# memory.net
KiCad netlist of a schematic drawn in Altium Designer
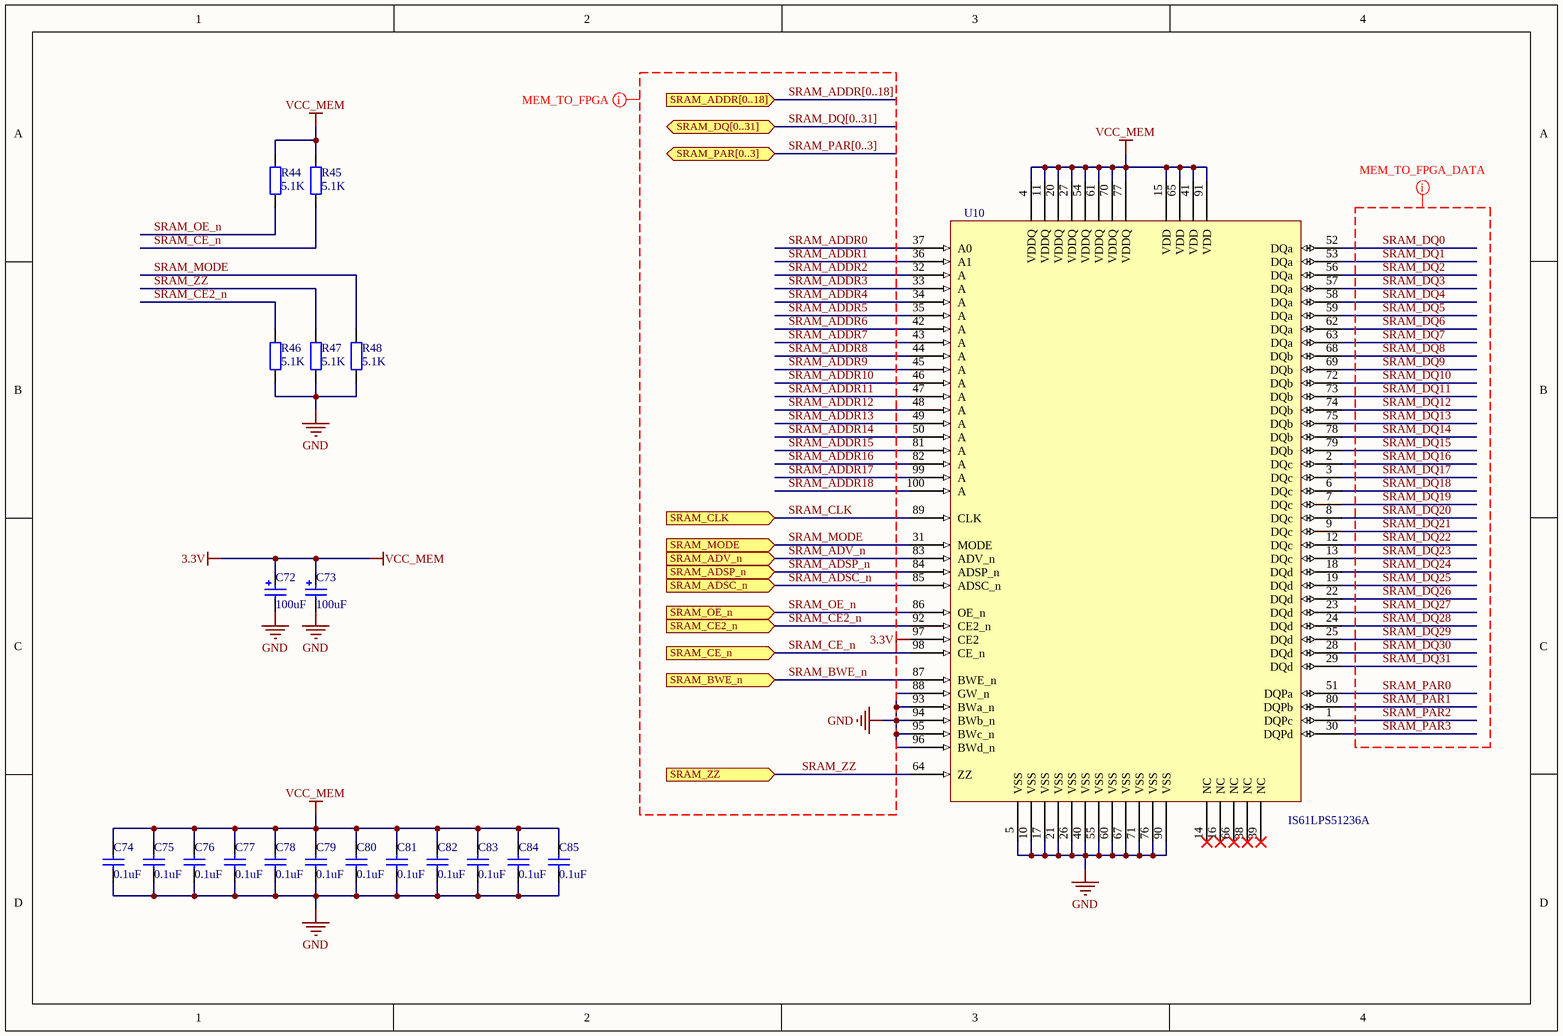
[diagram p0: memory.SchDoc]

(export (version "E")
  (design (tool "Eeschema 10.0.6"))
  (components
    (comp (ref "C72")
      (value "100uF")
      (footprint "C1206_POLARIZED")
      (description "Polarized Capacitor (Axial)")
      (fields (field (name "Comment") "Cap Pol2") (field (name "PUBLISHER") "Altium Limited"))
      (libsource (lib "Miscellaneous Devices") (part "Cap Pol2"))
    )
    (comp (ref "C73")
      (value "100uF")
      (footprint "C1206_POLARIZED")
      (description "Polarized Capacitor (Axial)")
      (fields (field (name "Comment") "Cap Pol2") (field (name "PUBLISHER") "Altium Limited"))
      (libsource (lib "Miscellaneous Devices") (part "Cap Pol2"))
    )
    (comp (ref "C74")
      (value "0.1uF")
      (footprint "0402")
      (description "Capacitor")
      (fields (field (name "Comment") "Cap") (field (name "PUBLISHER") "Altium Limited"))
      (libsource (lib "Miscellaneous Devices") (part "Cap"))
    )
    (comp (ref "C75")
      (value "0.1uF")
      (footprint "0402")
      (description "Capacitor")
      (fields (field (name "Comment") "Cap") (field (name "PUBLISHER") "Altium Limited"))
      (libsource (lib "Miscellaneous Devices") (part "Cap"))
    )
    (comp (ref "C76")
      (value "0.1uF")
      (footprint "0402")
      (description "Capacitor")
      (fields (field (name "Comment") "Cap") (field (name "PUBLISHER") "Altium Limited"))
      (libsource (lib "Miscellaneous Devices") (part "Cap"))
    )
    (comp (ref "C77")
      (value "0.1uF")
      (footprint "0402")
      (description "Capacitor")
      (fields (field (name "Comment") "Cap") (field (name "PUBLISHER") "Altium Limited"))
      (libsource (lib "Miscellaneous Devices") (part "Cap"))
    )
    (comp (ref "C78")
      (value "0.1uF")
      (footprint "0402")
      (description "Capacitor")
      (fields (field (name "Comment") "Cap") (field (name "PUBLISHER") "Altium Limited"))
      (libsource (lib "Miscellaneous Devices") (part "Cap"))
    )
    (comp (ref "C79")
      (value "0.1uF")
      (footprint "0402")
      (description "Capacitor")
      (fields (field (name "Comment") "Cap") (field (name "PUBLISHER") "Altium Limited"))
      (libsource (lib "Miscellaneous Devices") (part "Cap"))
    )
    (comp (ref "C80")
      (value "0.1uF")
      (footprint "0402")
      (description "Capacitor")
      (fields (field (name "Comment") "Cap") (field (name "PUBLISHER") "Altium Limited"))
      (libsource (lib "Miscellaneous Devices") (part "Cap"))
    )
    (comp (ref "C81")
      (value "0.1uF")
      (footprint "0402")
      (description "Capacitor")
      (fields (field (name "Comment") "Cap") (field (name "PUBLISHER") "Altium Limited"))
      (libsource (lib "Miscellaneous Devices") (part "Cap"))
    )
    (comp (ref "C82")
      (value "0.1uF")
      (footprint "0402")
      (description "Capacitor")
      (fields (field (name "Comment") "Cap") (field (name "PUBLISHER") "Altium Limited"))
      (libsource (lib "Miscellaneous Devices") (part "Cap"))
    )
    (comp (ref "C83")
      (value "0.1uF")
      (footprint "0402")
      (description "Capacitor")
      (fields (field (name "Comment") "Cap") (field (name "PUBLISHER") "Altium Limited"))
      (libsource (lib "Miscellaneous Devices") (part "Cap"))
    )
    (comp (ref "C84")
      (value "0.1uF")
      (footprint "0402")
      (description "Capacitor")
      (fields (field (name "Comment") "Cap") (field (name "PUBLISHER") "Altium Limited"))
      (libsource (lib "Miscellaneous Devices") (part "Cap"))
    )
    (comp (ref "C85")
      (value "0.1uF")
      (footprint "0402")
      (description "Capacitor")
      (fields (field (name "Comment") "Cap") (field (name "PUBLISHER") "Altium Limited"))
      (libsource (lib "Miscellaneous Devices") (part "Cap"))
    )
    (comp (ref "R44")
      (value "5.1K")
      (footprint "J1-0603")
      (description "Resistor")
      (fields (field (name "Comment") "Res2") (field (name "PUBLISHER") "Altium Limited"))
      (libsource (lib "Miscellaneous Devices") (part "Res2"))
    )
    (comp (ref "R45")
      (value "5.1K")
      (footprint "J1-0603")
      (description "Resistor")
      (fields (field (name "Comment") "Res2") (field (name "PUBLISHER") "Altium Limited"))
      (libsource (lib "Miscellaneous Devices") (part "Res2"))
    )
    (comp (ref "R46")
      (value "5.1K")
      (footprint "J1-0603")
      (description "Resistor")
      (fields (field (name "Comment") "Res2") (field (name "PUBLISHER") "Altium Limited"))
      (libsource (lib "Miscellaneous Devices") (part "Res2"))
    )
    (comp (ref "R47")
      (value "5.1K")
      (footprint "J1-0603")
      (description "Resistor")
      (fields (field (name "Comment") "Res2") (field (name "PUBLISHER") "Altium Limited"))
      (libsource (lib "Miscellaneous Devices") (part "Res2"))
    )
    (comp (ref "R48")
      (value "5.1K")
      (footprint "J1-0603")
      (description "Resistor")
      (fields (field (name "Comment") "Res2") (field (name "PUBLISHER") "Altium Limited"))
      (libsource (lib "Miscellaneous Devices") (part "Res2"))
    )
    (comp (ref "U10")
      (value "IS61LPS51236A")
      (footprint "TQFP100")
      (description "18Mb 36-bit SRAM")
      (libsource (lib "FPGA_board") (part "IS61LPS51236A"))
    )
  )
  (nets
    (net (code "1") (name "/SRAM_ADDR0") (class "Default")
      (node (ref "U10") (pin "37") (pinfunction "A0_37") (pintype "input"))
    )
    (net (code "2") (name "/SRAM_ADDR1") (class "Default")
      (node (ref "U10") (pin "36") (pinfunction "A1_36") (pintype "input"))
    )
    (net (code "3") (name "/SRAM_ADDR2") (class "Default")
      (node (ref "U10") (pin "32") (pinfunction "A_32") (pintype "input"))
    )
    (net (code "4") (name "/SRAM_ADDR3") (class "Default")
      (node (ref "U10") (pin "33") (pinfunction "A_33") (pintype "input"))
    )
    (net (code "5") (name "/SRAM_ADDR4") (class "Default")
      (node (ref "U10") (pin "34") (pinfunction "A_34") (pintype "input"))
    )
    (net (code "6") (name "/SRAM_ADDR5") (class "Default")
      (node (ref "U10") (pin "35") (pinfunction "A_35") (pintype "input"))
    )
    (net (code "7") (name "/SRAM_ADDR6") (class "Default")
      (node (ref "U10") (pin "42") (pinfunction "A_42") (pintype "input"))
    )
    (net (code "8") (name "/SRAM_ADDR7") (class "Default")
      (node (ref "U10") (pin "43") (pinfunction "A_43") (pintype "input"))
    )
    (net (code "9") (name "/SRAM_ADDR8") (class "Default")
      (node (ref "U10") (pin "44") (pinfunction "A_44") (pintype "input"))
    )
    (net (code "10") (name "/SRAM_ADDR9") (class "Default")
      (node (ref "U10") (pin "45") (pinfunction "A_45") (pintype "input"))
    )
    (net (code "11") (name "/SRAM_ADDR10") (class "Default")
      (node (ref "U10") (pin "46") (pinfunction "A_46") (pintype "input"))
    )
    (net (code "12") (name "/SRAM_ADDR11") (class "Default")
      (node (ref "U10") (pin "47") (pinfunction "A_47") (pintype "input"))
    )
    (net (code "13") (name "/SRAM_ADDR12") (class "Default")
      (node (ref "U10") (pin "48") (pinfunction "A_48") (pintype "input"))
    )
    (net (code "14") (name "/SRAM_ADDR13") (class "Default")
      (node (ref "U10") (pin "49") (pinfunction "A_49") (pintype "input"))
    )
    (net (code "15") (name "/SRAM_ADDR14") (class "Default")
      (node (ref "U10") (pin "50") (pinfunction "A_50") (pintype "input"))
    )
    (net (code "16") (name "/SRAM_ADDR15") (class "Default")
      (node (ref "U10") (pin "81") (pinfunction "A_81") (pintype "input"))
    )
    (net (code "17") (name "/SRAM_ADDR16") (class "Default")
      (node (ref "U10") (pin "82") (pinfunction "A_82") (pintype "input"))
    )
    (net (code "18") (name "/SRAM_ADDR17") (class "Default")
      (node (ref "U10") (pin "99") (pinfunction "A_99") (pintype "input"))
    )
    (net (code "19") (name "/SRAM_ADDR18") (class "Default")
      (node (ref "U10") (pin "100") (pinfunction "A_100") (pintype "input"))
    )
    (net (code "21") (name "/SRAM_ADSC_n") (class "Default")
      (node (ref "U10") (pin "85") (pinfunction "ADSC_n_85") (pintype "input"))
    )
    (net (code "22") (name "/SRAM_ADSP_n") (class "Default")
      (node (ref "U10") (pin "84") (pinfunction "ADSP_n_84") (pintype "input"))
    )
    (net (code "23") (name "/SRAM_ADV_n") (class "Default")
      (node (ref "U10") (pin "83") (pinfunction "ADV_n_83") (pintype "input"))
    )
    (net (code "24") (name "/SRAM_BWE_n") (class "Default")
      (node (ref "U10") (pin "87") (pinfunction "BWE_n_87") (pintype "input"))
    )
    (net (code "25") (name "/SRAM_CE2_n") (class "Default")
      (node (ref "R46") (pin "1") (pinfunction "1_1") (pintype "passive"))
      (node (ref "U10") (pin "92") (pinfunction "CE2_n_92") (pintype "input"))
    )
    (net (code "26") (name "/SRAM_CE_n") (class "Default")
      (node (ref "R45") (pin "2") (pinfunction "2_2") (pintype "passive"))
      (node (ref "U10") (pin "98") (pinfunction "CE_n_98") (pintype "input"))
    )
    (net (code "27") (name "/SRAM_CLK") (class "Default")
      (node (ref "U10") (pin "89") (pinfunction "CLK_89") (pintype "input"))
    )
    (net (code "28") (name "/SRAM_DQ0") (class "Default")
      (node (ref "U10") (pin "52") (pinfunction "DQa_52") (pintype "bidirectional"))
    )
    (net (code "29") (name "/SRAM_DQ1") (class "Default")
      (node (ref "U10") (pin "53") (pinfunction "DQa_53") (pintype "bidirectional"))
    )
    (net (code "30") (name "/SRAM_DQ2") (class "Default")
      (node (ref "U10") (pin "56") (pinfunction "DQa_56") (pintype "bidirectional"))
    )
    (net (code "31") (name "/SRAM_DQ3") (class "Default")
      (node (ref "U10") (pin "57") (pinfunction "DQa_57") (pintype "bidirectional"))
    )
    (net (code "32") (name "/SRAM_DQ4") (class "Default")
      (node (ref "U10") (pin "58") (pinfunction "DQa_58") (pintype "bidirectional"))
    )
    (net (code "33") (name "/SRAM_DQ5") (class "Default")
      (node (ref "U10") (pin "59") (pinfunction "DQa_59") (pintype "bidirectional"))
    )
    (net (code "34") (name "/SRAM_DQ6") (class "Default")
      (node (ref "U10") (pin "62") (pinfunction "DQa_62") (pintype "bidirectional"))
    )
    (net (code "35") (name "/SRAM_DQ7") (class "Default")
      (node (ref "U10") (pin "63") (pinfunction "DQa_63") (pintype "bidirectional"))
    )
    (net (code "36") (name "/SRAM_DQ8") (class "Default")
      (node (ref "U10") (pin "68") (pinfunction "DQb_68") (pintype "bidirectional"))
    )
    (net (code "37") (name "/SRAM_DQ9") (class "Default")
      (node (ref "U10") (pin "69") (pinfunction "DQb_69") (pintype "bidirectional"))
    )
    (net (code "38") (name "/SRAM_DQ10") (class "Default")
      (node (ref "U10") (pin "72") (pinfunction "DQb_72") (pintype "bidirectional"))
    )
    (net (code "39") (name "/SRAM_DQ11") (class "Default")
      (node (ref "U10") (pin "73") (pinfunction "DQb_73") (pintype "bidirectional"))
    )
    (net (code "40") (name "/SRAM_DQ12") (class "Default")
      (node (ref "U10") (pin "74") (pinfunction "DQb_74") (pintype "bidirectional"))
    )
    (net (code "41") (name "/SRAM_DQ13") (class "Default")
      (node (ref "U10") (pin "75") (pinfunction "DQb_75") (pintype "bidirectional"))
    )
    (net (code "42") (name "/SRAM_DQ14") (class "Default")
      (node (ref "U10") (pin "78") (pinfunction "DQb_78") (pintype "bidirectional"))
    )
    (net (code "43") (name "/SRAM_DQ15") (class "Default")
      (node (ref "U10") (pin "79") (pinfunction "DQb_79") (pintype "bidirectional"))
    )
    (net (code "44") (name "/SRAM_DQ16") (class "Default")
      (node (ref "U10") (pin "2") (pinfunction "DQc_2") (pintype "bidirectional"))
    )
    (net (code "45") (name "/SRAM_DQ17") (class "Default")
      (node (ref "U10") (pin "3") (pinfunction "DQc_3") (pintype "bidirectional"))
    )
    (net (code "46") (name "/SRAM_DQ18") (class "Default")
      (node (ref "U10") (pin "6") (pinfunction "DQc_6") (pintype "bidirectional"))
    )
    (net (code "47") (name "/SRAM_DQ19") (class "Default")
      (node (ref "U10") (pin "7") (pinfunction "DQc_7") (pintype "bidirectional"))
    )
    (net (code "48") (name "/SRAM_DQ20") (class "Default")
      (node (ref "U10") (pin "8") (pinfunction "DQc_8") (pintype "bidirectional"))
    )
    (net (code "49") (name "/SRAM_DQ21") (class "Default")
      (node (ref "U10") (pin "9") (pinfunction "DQc_9") (pintype "bidirectional"))
    )
    (net (code "50") (name "/SRAM_DQ22") (class "Default")
      (node (ref "U10") (pin "12") (pinfunction "DQc_12") (pintype "bidirectional"))
    )
    (net (code "51") (name "/SRAM_DQ23") (class "Default")
      (node (ref "U10") (pin "13") (pinfunction "DQc_13") (pintype "bidirectional"))
    )
    (net (code "52") (name "/SRAM_DQ24") (class "Default")
      (node (ref "U10") (pin "18") (pinfunction "DQd_18") (pintype "bidirectional"))
    )
    (net (code "53") (name "/SRAM_DQ25") (class "Default")
      (node (ref "U10") (pin "19") (pinfunction "DQd_19") (pintype "bidirectional"))
    )
    (net (code "54") (name "/SRAM_DQ26") (class "Default")
      (node (ref "U10") (pin "22") (pinfunction "DQd_22") (pintype "bidirectional"))
    )
    (net (code "55") (name "/SRAM_DQ27") (class "Default")
      (node (ref "U10") (pin "23") (pinfunction "DQd_23") (pintype "bidirectional"))
    )
    (net (code "56") (name "/SRAM_DQ28") (class "Default")
      (node (ref "U10") (pin "24") (pinfunction "DQd_24") (pintype "bidirectional"))
    )
    (net (code "57") (name "/SRAM_DQ29") (class "Default")
      (node (ref "U10") (pin "25") (pinfunction "DQd_25") (pintype "bidirectional"))
    )
    (net (code "58") (name "/SRAM_DQ30") (class "Default")
      (node (ref "U10") (pin "28") (pinfunction "DQd_28") (pintype "bidirectional"))
    )
    (net (code "59") (name "/SRAM_DQ31") (class "Default")
      (node (ref "U10") (pin "29") (pinfunction "DQd_29") (pintype "bidirectional"))
    )
    (net (code "61") (name "/SRAM_MODE") (class "Default")
      (node (ref "R48") (pin "1") (pinfunction "1_1") (pintype "passive"))
      (node (ref "U10") (pin "31") (pinfunction "MODE_31") (pintype "input"))
    )
    (net (code "62") (name "/SRAM_OE_n") (class "Default")
      (node (ref "R44") (pin "2") (pinfunction "2_2") (pintype "passive"))
      (node (ref "U10") (pin "86") (pinfunction "OE_n_86") (pintype "input"))
    )
    (net (code "63") (name "/SRAM_PAR0") (class "Default")
      (node (ref "U10") (pin "51") (pinfunction "DQPa_51") (pintype "bidirectional"))
    )
    (net (code "64") (name "/SRAM_PAR1") (class "Default")
      (node (ref "U10") (pin "80") (pinfunction "DQPb_80") (pintype "bidirectional"))
    )
    (net (code "65") (name "/SRAM_PAR2") (class "Default")
      (node (ref "U10") (pin "1") (pinfunction "DQPc_1") (pintype "bidirectional"))
    )
    (net (code "66") (name "/SRAM_PAR3") (class "Default")
      (node (ref "U10") (pin "30") (pinfunction "DQPd_30") (pintype "bidirectional"))
    )
    (net (code "68") (name "/SRAM_ZZ") (class "Default")
      (node (ref "R47") (pin "1") (pinfunction "1_1") (pintype "passive"))
      (node (ref "U10") (pin "64") (pinfunction "ZZ_64") (pintype "input"))
    )
    (net (code "69") (name "3.3V") (class "Default")
      (node (ref "C72") (pin "1") (pinfunction "1_1") (pintype "passive"))
      (node (ref "C73") (pin "1") (pinfunction "1_1") (pintype "passive"))
      (node (ref "C74") (pin "1") (pinfunction "1_1") (pintype "passive"))
      (node (ref "C75") (pin "1") (pinfunction "1_1") (pintype "passive"))
      (node (ref "C76") (pin "1") (pinfunction "1_1") (pintype "passive"))
      (node (ref "C77") (pin "1") (pinfunction "1_1") (pintype "passive"))
      (node (ref "C78") (pin "1") (pinfunction "1_1") (pintype "passive"))
      (node (ref "C79") (pin "1") (pinfunction "1_1") (pintype "passive"))
      (node (ref "C80") (pin "1") (pinfunction "1_1") (pintype "passive"))
      (node (ref "C81") (pin "1") (pinfunction "1_1") (pintype "passive"))
      (node (ref "C82") (pin "1") (pinfunction "1_1") (pintype "passive"))
      (node (ref "C83") (pin "1") (pinfunction "1_1") (pintype "passive"))
      (node (ref "C84") (pin "1") (pinfunction "1_1") (pintype "passive"))
      (node (ref "C85") (pin "1") (pinfunction "1_1") (pintype "passive"))
      (node (ref "R44") (pin "1") (pinfunction "1_1") (pintype "passive"))
      (node (ref "R45") (pin "1") (pinfunction "1_1") (pintype "passive"))
      (node (ref "U10") (pin "11") (pinfunction "VDDQ_11") (pintype "power_in"))
      (node (ref "U10") (pin "15") (pinfunction "VDD_15") (pintype "power_in"))
      (node (ref "U10") (pin "20") (pinfunction "VDDQ_20") (pintype "power_in"))
      (node (ref "U10") (pin "27") (pinfunction "VDDQ_27") (pintype "power_in"))
      (node (ref "U10") (pin "4") (pinfunction "VDDQ_4") (pintype "power_in"))
      (node (ref "U10") (pin "41") (pinfunction "VDD_41") (pintype "power_in"))
      (node (ref "U10") (pin "54") (pinfunction "VDDQ_54") (pintype "power_in"))
      (node (ref "U10") (pin "61") (pinfunction "VDDQ_61") (pintype "power_in"))
      (node (ref "U10") (pin "65") (pinfunction "VDD_65") (pintype "power_in"))
      (node (ref "U10") (pin "70") (pinfunction "VDDQ_70") (pintype "power_in"))
      (node (ref "U10") (pin "77") (pinfunction "VDDQ_77") (pintype "power_in"))
      (node (ref "U10") (pin "91") (pinfunction "VDD_91") (pintype "power_in"))
      (node (ref "U10") (pin "97") (pinfunction "CE2_97") (pintype "input"))
    )
    (net (code "70") (name "GND") (class "Default")
      (node (ref "C72") (pin "2") (pinfunction "2_2") (pintype "passive"))
      (node (ref "C73") (pin "2") (pinfunction "2_2") (pintype "passive"))
      (node (ref "C74") (pin "2") (pinfunction "2_2") (pintype "passive"))
      (node (ref "C75") (pin "2") (pinfunction "2_2") (pintype "passive"))
      (node (ref "C76") (pin "2") (pinfunction "2_2") (pintype "passive"))
      (node (ref "C77") (pin "2") (pinfunction "2_2") (pintype "passive"))
      (node (ref "C78") (pin "2") (pinfunction "2_2") (pintype "passive"))
      (node (ref "C79") (pin "2") (pinfunction "2_2") (pintype "passive"))
      (node (ref "C80") (pin "2") (pinfunction "2_2") (pintype "passive"))
      (node (ref "C81") (pin "2") (pinfunction "2_2") (pintype "passive"))
      (node (ref "C82") (pin "2") (pinfunction "2_2") (pintype "passive"))
      (node (ref "C83") (pin "2") (pinfunction "2_2") (pintype "passive"))
      (node (ref "C84") (pin "2") (pinfunction "2_2") (pintype "passive"))
      (node (ref "C85") (pin "2") (pinfunction "2_2") (pintype "passive"))
      (node (ref "R46") (pin "2") (pinfunction "2_2") (pintype "passive"))
      (node (ref "R47") (pin "2") (pinfunction "2_2") (pintype "passive"))
      (node (ref "R48") (pin "2") (pinfunction "2_2") (pintype "passive"))
      (node (ref "U10") (pin "10") (pinfunction "VSS_10") (pintype "power_in"))
      (node (ref "U10") (pin "17") (pinfunction "VSS_17") (pintype "power_in"))
      (node (ref "U10") (pin "21") (pinfunction "VSS_21") (pintype "power_in"))
      (node (ref "U10") (pin "26") (pinfunction "VSS_26") (pintype "power_in"))
      (node (ref "U10") (pin "40") (pinfunction "VSS_40") (pintype "power_in"))
      (node (ref "U10") (pin "5") (pinfunction "VSS_5") (pintype "power_in"))
      (node (ref "U10") (pin "55") (pinfunction "VSS_55") (pintype "power_in"))
      (node (ref "U10") (pin "60") (pinfunction "VSS_60") (pintype "power_in"))
      (node (ref "U10") (pin "67") (pinfunction "VSS_67") (pintype "power_in"))
      (node (ref "U10") (pin "71") (pinfunction "VSS_71") (pintype "power_in"))
      (node (ref "U10") (pin "76") (pinfunction "VSS_76") (pintype "power_in"))
      (node (ref "U10") (pin "88") (pinfunction "GW_n_88") (pintype "input"))
      (node (ref "U10") (pin "90") (pinfunction "VSS_90") (pintype "power_in"))
      (node (ref "U10") (pin "93") (pinfunction "BWa_n_93") (pintype "input"))
      (node (ref "U10") (pin "94") (pinfunction "BWb_n_94") (pintype "input"))
      (node (ref "U10") (pin "95") (pinfunction "BWc_n_95") (pintype "input"))
      (node (ref "U10") (pin "96") (pinfunction "BWd_n_96") (pintype "input"))
    )
    (net (code "71") (name "unconnected-(U10-NC-Pad14)") (class "Default")
      (node (ref "U10") (pin "14") (pinfunction "NC_14") (pintype "passive+no_connect"))
    )
    (net (code "72") (name "unconnected-(U10-NC-Pad16)") (class "Default")
      (node (ref "U10") (pin "16") (pinfunction "NC_16") (pintype "passive+no_connect"))
    )
    (net (code "73") (name "unconnected-(U10-NC-Pad38)") (class "Default")
      (node (ref "U10") (pin "38") (pinfunction "NC_38") (pintype "passive+no_connect"))
    )
    (net (code "74") (name "unconnected-(U10-NC-Pad39)") (class "Default")
      (node (ref "U10") (pin "39") (pinfunction "NC_39") (pintype "passive+no_connect"))
    )
    (net (code "75") (name "unconnected-(U10-NC-Pad66)") (class "Default")
      (node (ref "U10") (pin "66") (pinfunction "NC_66") (pintype "passive+no_connect"))
    )
  )
)
